# osi-brain_rev_1.net
KiCad netlist of a schematic drawn in EAGLE
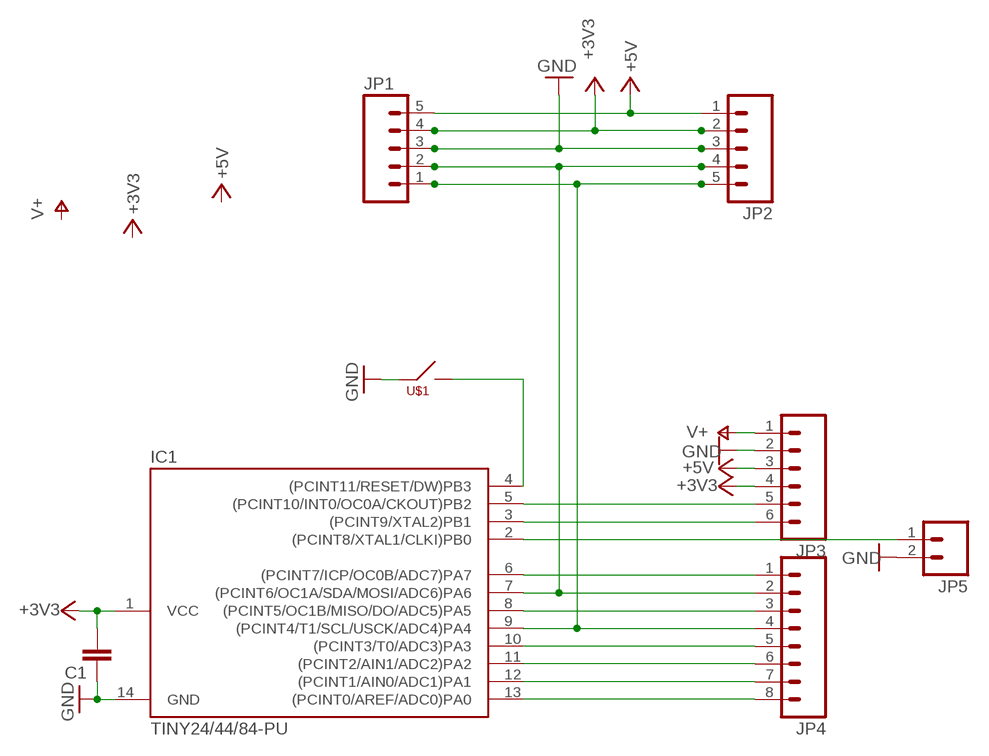
[diagram p0: schematic, sheet 1]

(export (version "E")
  (design (tool "Eeschema 10.0.6"))
  (components
    (comp (ref "C1")
      (value "CAPKIT")
      (footprint "eagle-import:CAP-PTH-SMALL-KIT")
      (libsource (lib "eagle-import") (part "CAPKIT"))
    )
    (comp (ref "IC1")
      (value "TINY24/44/84-PU")
      (footprint "eagle-import:DIL14")
      (libsource (lib "eagle-import") (part "TINY24/44/84-PU"))
    )
    (comp (ref "JP1")
      (value "M05PTH")
      (footprint "eagle-import:1X05")
      (libsource (lib "eagle-import") (part "M05PTH"))
    )
    (comp (ref "JP2")
      (value "M05PTH")
      (footprint "eagle-import:1X05")
      (libsource (lib "eagle-import") (part "M05PTH"))
    )
    (comp (ref "JP3")
      (value "M06SIP")
      (footprint "eagle-import:1X06")
      (libsource (lib "eagle-import") (part "M06SIP"))
    )
    (comp (ref "JP4")
      (value "M081X08")
      (footprint "eagle-import:1X08")
      (libsource (lib "eagle-import") (part "M081X08"))
    )
    (comp (ref "JP5")
      (value "M021X02_NO_SILK")
      (footprint "eagle-import:1X02_NO_SILK")
      (libsource (lib "eagle-import") (part "M021X02_NO_SILK"))
    )
    (comp (ref "U$1")
      (value "PTS635_SWITCH")
      (footprint "eagle-import:PTS635_SWITCH")
      (libsource (lib "eagle-import") (part "PTS635_SWITCH"))
    )
  )
  (nets
    (net (code "1") (name "+3V3") (class "Default")
      (node (ref "C1") (pin "2") (pinfunction "2_2") (pintype "passive"))
      (node (ref "IC1") (pin "1") (pinfunction "VCC_1") (pintype "power_in"))
      (node (ref "JP1") (pin "4") (pinfunction "4_4") (pintype "passive"))
      (node (ref "JP2") (pin "2") (pinfunction "2_2") (pintype "passive"))
      (node (ref "JP3") (pin "4") (pinfunction "4_4") (pintype "passive"))
    )
    (net (code "2") (name "+5V") (class "Default")
      (node (ref "JP1") (pin "5") (pinfunction "5_5") (pintype "passive"))
      (node (ref "JP2") (pin "1") (pinfunction "1_1") (pintype "passive"))
      (node (ref "JP3") (pin "3") (pinfunction "3_3") (pintype "passive"))
    )
    (net (code "3") (name "GND") (class "Default")
      (node (ref "C1") (pin "1") (pinfunction "1_1") (pintype "passive"))
      (node (ref "IC1") (pin "14") (pinfunction "GND_14") (pintype "power_in"))
      (node (ref "JP1") (pin "3") (pinfunction "3_3") (pintype "passive"))
      (node (ref "JP2") (pin "3") (pinfunction "3_3") (pintype "passive"))
      (node (ref "JP3") (pin "2") (pinfunction "2_2") (pintype "passive"))
      (node (ref "JP5") (pin "2") (pinfunction "2_2") (pintype "passive"))
      (node (ref "U$1") (pin "P$1") (pinfunction "P$1_P$1") (pintype "bidirectional"))
    )
    (net (code "4") (name "Net-(IC1-(PCINT0{slash}AREF{slash}ADC0)PA0)") (class "Default")
      (node (ref "IC1") (pin "13") (pinfunction "(PCINT0/AREF/ADC0)PA0_13") (pintype "bidirectional"))
      (node (ref "JP4") (pin "8") (pinfunction "8_8") (pintype "passive"))
    )
    (net (code "5") (name "Net-(IC1-(PCINT1{slash}AIN0{slash}ADC1)PA1)") (class "Default")
      (node (ref "IC1") (pin "12") (pinfunction "(PCINT1/AIN0/ADC1)PA1_12") (pintype "bidirectional"))
      (node (ref "JP4") (pin "7") (pinfunction "7_7") (pintype "passive"))
    )
    (net (code "6") (name "Net-(IC1-(PCINT2{slash}AIN1{slash}ADC2)PA2)") (class "Default")
      (node (ref "IC1") (pin "11") (pinfunction "(PCINT2/AIN1/ADC2)PA2_11") (pintype "bidirectional"))
      (node (ref "JP4") (pin "6") (pinfunction "6_6") (pintype "passive"))
    )
    (net (code "7") (name "Net-(IC1-(PCINT3{slash}T0{slash}ADC3)PA3)") (class "Default")
      (node (ref "IC1") (pin "10") (pinfunction "(PCINT3/T0/ADC3)PA3_10") (pintype "bidirectional"))
      (node (ref "JP4") (pin "5") (pinfunction "5_5") (pintype "passive"))
    )
    (net (code "8") (name "Net-(IC1-(PCINT4{slash}T1{slash}SCL{slash}USCK{slash}ADC4)PA4)") (class "Default")
      (node (ref "IC1") (pin "9") (pinfunction "(PCINT4/T1/SCL/USCK/ADC4)PA4_9") (pintype "bidirectional"))
      (node (ref "JP1") (pin "1") (pinfunction "1_1") (pintype "passive"))
      (node (ref "JP2") (pin "5") (pinfunction "5_5") (pintype "passive"))
      (node (ref "JP4") (pin "4") (pinfunction "4_4") (pintype "passive"))
    )
    (net (code "9") (name "Net-(IC1-(PCINT5{slash}OC1B{slash}MISO{slash}DO{slash}ADC5)PA5)") (class "Default")
      (node (ref "IC1") (pin "8") (pinfunction "(PCINT5/OC1B/MISO/DO/ADC5)PA5_8") (pintype "bidirectional"))
      (node (ref "JP4") (pin "3") (pinfunction "3_3") (pintype "passive"))
    )
    (net (code "10") (name "Net-(IC1-(PCINT6{slash}OC1A{slash}SDA{slash}MOSI{slash}ADC6)PA6)") (class "Default")
      (node (ref "IC1") (pin "7") (pinfunction "(PCINT6/OC1A/SDA/MOSI/ADC6)PA6_7") (pintype "bidirectional"))
      (node (ref "JP1") (pin "2") (pinfunction "2_2") (pintype "passive"))
      (node (ref "JP2") (pin "4") (pinfunction "4_4") (pintype "passive"))
      (node (ref "JP4") (pin "2") (pinfunction "2_2") (pintype "passive"))
    )
    (net (code "11") (name "Net-(IC1-(PCINT7{slash}ICP{slash}OC0B{slash}ADC7)PA7)") (class "Default")
      (node (ref "IC1") (pin "6") (pinfunction "(PCINT7/ICP/OC0B/ADC7)PA7_6") (pintype "bidirectional"))
      (node (ref "JP4") (pin "1") (pinfunction "1_1") (pintype "passive"))
    )
    (net (code "12") (name "Net-(IC1-(PCINT8{slash}XTAL1{slash}CLKI)PB0)") (class "Default")
      (node (ref "IC1") (pin "2") (pinfunction "(PCINT8/XTAL1/CLKI)PB0_2") (pintype "bidirectional"))
      (node (ref "JP5") (pin "1") (pinfunction "1_1") (pintype "passive"))
    )
    (net (code "13") (name "Net-(IC1-(PCINT9{slash}XTAL2)PB1)") (class "Default")
      (node (ref "IC1") (pin "3") (pinfunction "(PCINT9/XTAL2)PB1_3") (pintype "bidirectional"))
      (node (ref "JP3") (pin "6") (pinfunction "6_6") (pintype "passive"))
    )
    (net (code "14") (name "Net-(IC1-(PCINT10{slash}INT0{slash}OC0A{slash}CKOUT)PB2)") (class "Default")
      (node (ref "IC1") (pin "5") (pinfunction "(PCINT10/INT0/OC0A/CKOUT)PB2_5") (pintype "bidirectional"))
      (node (ref "JP3") (pin "5") (pinfunction "5_5") (pintype "passive"))
    )
    (net (code "15") (name "Net-(IC1-(PCINT11{slash}RESET{slash}DW)PB3)") (class "Default")
      (node (ref "IC1") (pin "4") (pinfunction "(PCINT11/RESET/DW)PB3_4") (pintype "bidirectional"))
      (node (ref "U$1") (pin "P$2") (pinfunction "P$2_P$2") (pintype "bidirectional"))
    )
    (net (code "16") (name "V+") (class "Default")
      (node (ref "JP3") (pin "1") (pinfunction "1_1") (pintype "passive"))
    )
  )
)
